# CablineDP.net
KiCad netlist of a schematic drawn in Altium Designer
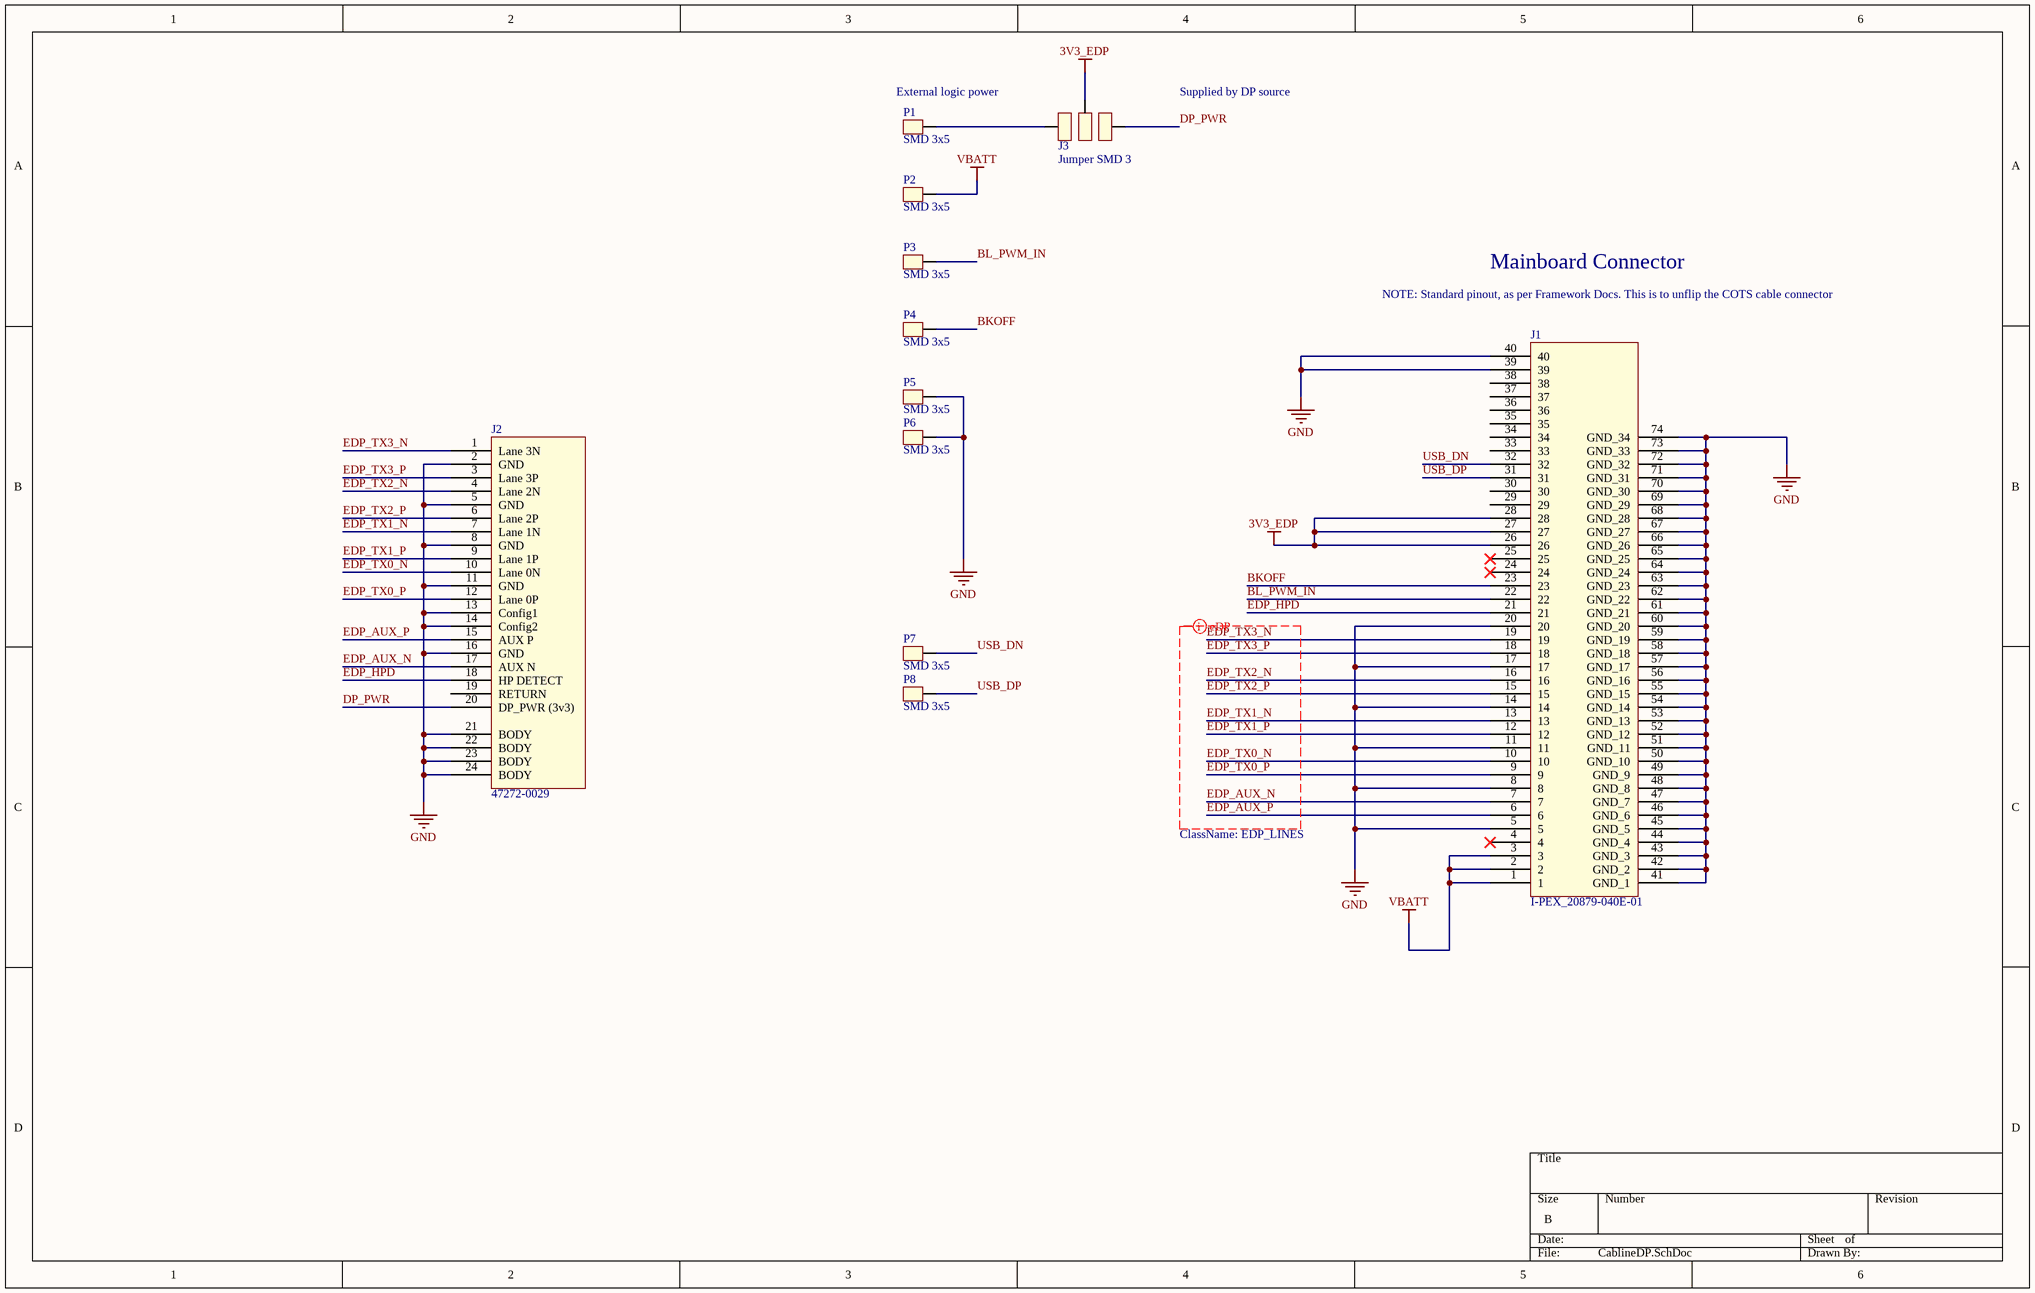
[diagram p0: CablineDP.SchDoc]

(export (version "E")
  (design (tool "Eeschema 10.0.6"))
  (components
    (comp (ref "J1")
      (value "I-PEX_20879-040E-01")
      (footprint "I-PEX_20879-040E-01")
      (libsource (lib "KBuchka-IntLib") (part "I-PEX_20879-040E-01"))
    )
    (comp (ref "J2")
      (value "47272-0029")
      (footprint "47272-0029")
      (description "Molex displayport connector")
      (libsource (lib "KBuchka-IntLib") (part "47272-0029"))
    )
    (comp (ref "J3")
      (value "Jumper SMD 3")
      (footprint "Jumper SMD 3")
      (libsource (lib "KBuchka-IntLib") (part "Jumper SMD 3"))
    )
    (comp (ref "P1")
      (value "SMD 3x5")
      (footprint "SMD 3x5")
      (libsource (lib "KBuchka-IntLib") (part "SMD 3x5"))
    )
    (comp (ref "P2")
      (value "SMD 3x5")
      (footprint "SMD 3x5")
      (libsource (lib "KBuchka-IntLib") (part "SMD 3x5"))
    )
    (comp (ref "P3")
      (value "SMD 3x5")
      (footprint "SMD 3x5")
      (libsource (lib "KBuchka-IntLib") (part "SMD 3x5"))
    )
    (comp (ref "P4")
      (value "SMD 3x5")
      (footprint "SMD 3x5")
      (libsource (lib "KBuchka-IntLib") (part "SMD 3x5"))
    )
    (comp (ref "P5")
      (value "SMD 3x5")
      (footprint "SMD 3x5")
      (libsource (lib "KBuchka-IntLib") (part "SMD 3x5"))
    )
    (comp (ref "P6")
      (value "SMD 3x5")
      (footprint "SMD 3x5")
      (libsource (lib "KBuchka-IntLib") (part "SMD 3x5"))
    )
    (comp (ref "P7")
      (value "SMD 3x5")
      (footprint "SMD 3x5")
      (libsource (lib "KBuchka-IntLib") (part "SMD 3x5"))
    )
    (comp (ref "P8")
      (value "SMD 3x5")
      (footprint "SMD 3x5")
      (libsource (lib "KBuchka-IntLib") (part "SMD 3x5"))
    )
  )
  (nets
    (net (code "1") (name "/BKOFF") (class "Default")
      (node (ref "J1") (pin "23") (pinfunction "23_23") (pintype "passive"))
      (node (ref "P4") (pin "1") (pinfunction "1_1") (pintype "passive"))
    )
    (net (code "2") (name "/BL_PWM_IN") (class "Default")
      (node (ref "J1") (pin "22") (pinfunction "22_22") (pintype "passive"))
      (node (ref "P3") (pin "1") (pinfunction "1_1") (pintype "passive"))
    )
    (net (code "3") (name "/DP_PWR") (class "Default")
      (node (ref "J2") (pin "20") (pinfunction "DP_PWR_(3v3)_20") (pintype "passive"))
      (node (ref "J3") (pin "1") (pinfunction "1_1") (pintype "passive"))
    )
    (net (code "4") (name "/EDP_AUX_N") (class "Default")
      (node (ref "J1") (pin "7") (pinfunction "7_7") (pintype "passive"))
      (node (ref "J2") (pin "17") (pinfunction "AUX_N_17") (pintype "passive"))
    )
    (net (code "5") (name "/EDP_AUX_P") (class "Default")
      (node (ref "J1") (pin "6") (pinfunction "6_6") (pintype "passive"))
      (node (ref "J2") (pin "15") (pinfunction "AUX_P_15") (pintype "passive"))
    )
    (net (code "6") (name "/EDP_HPD") (class "Default")
      (node (ref "J1") (pin "21") (pinfunction "21_21") (pintype "passive"))
      (node (ref "J2") (pin "18") (pinfunction "HP_DETECT_18") (pintype "passive"))
    )
    (net (code "7") (name "/EDP_TX0_N") (class "Default")
      (node (ref "J1") (pin "10") (pinfunction "10_10") (pintype "passive"))
      (node (ref "J2") (pin "10") (pinfunction "Lane_0N_10") (pintype "passive"))
    )
    (net (code "8") (name "/EDP_TX0_P") (class "Default")
      (node (ref "J1") (pin "9") (pinfunction "9_9") (pintype "passive"))
      (node (ref "J2") (pin "12") (pinfunction "Lane_0P_12") (pintype "passive"))
    )
    (net (code "9") (name "/EDP_TX1_N") (class "Default")
      (node (ref "J1") (pin "13") (pinfunction "13_13") (pintype "passive"))
      (node (ref "J2") (pin "7") (pinfunction "Lane_1N_7") (pintype "passive"))
    )
    (net (code "10") (name "/EDP_TX1_P") (class "Default")
      (node (ref "J1") (pin "12") (pinfunction "12_12") (pintype "passive"))
      (node (ref "J2") (pin "9") (pinfunction "Lane_1P_9") (pintype "passive"))
    )
    (net (code "11") (name "/EDP_TX2_N") (class "Default")
      (node (ref "J1") (pin "16") (pinfunction "16_16") (pintype "passive"))
      (node (ref "J2") (pin "4") (pinfunction "Lane_2N_4") (pintype "passive"))
    )
    (net (code "12") (name "/EDP_TX2_P") (class "Default")
      (node (ref "J1") (pin "15") (pinfunction "15_15") (pintype "passive"))
      (node (ref "J2") (pin "6") (pinfunction "Lane_2P_6") (pintype "passive"))
    )
    (net (code "13") (name "/EDP_TX3_N") (class "Default")
      (node (ref "J1") (pin "19") (pinfunction "19_19") (pintype "passive"))
      (node (ref "J2") (pin "1") (pinfunction "Lane_3N_1") (pintype "passive"))
    )
    (net (code "14") (name "/EDP_TX3_P") (class "Default")
      (node (ref "J1") (pin "18") (pinfunction "18_18") (pintype "passive"))
      (node (ref "J2") (pin "3") (pinfunction "Lane_3P_3") (pintype "passive"))
    )
    (net (code "15") (name "/USB_DN") (class "Default")
      (node (ref "J1") (pin "32") (pinfunction "32_32") (pintype "passive"))
      (node (ref "P7") (pin "1") (pinfunction "1_1") (pintype "passive"))
    )
    (net (code "16") (name "/USB_DP") (class "Default")
      (node (ref "J1") (pin "31") (pinfunction "31_31") (pintype "passive"))
      (node (ref "P8") (pin "1") (pinfunction "1_1") (pintype "passive"))
    )
    (net (code "17") (name "3V3_EDP") (class "Default")
      (node (ref "J1") (pin "26") (pinfunction "26_26") (pintype "passive"))
      (node (ref "J1") (pin "27") (pinfunction "27_27") (pintype "passive"))
      (node (ref "J1") (pin "28") (pinfunction "28_28") (pintype "passive"))
      (node (ref "J3") (pin "2") (pinfunction "2_2") (pintype "passive"))
    )
    (net (code "18") (name "GND") (class "Default")
      (node (ref "J1") (pin "11") (pinfunction "11_11") (pintype "passive"))
      (node (ref "J1") (pin "14") (pinfunction "14_14") (pintype "passive"))
      (node (ref "J1") (pin "17") (pinfunction "17_17") (pintype "passive"))
      (node (ref "J1") (pin "20") (pinfunction "20_20") (pintype "passive"))
      (node (ref "J1") (pin "39") (pinfunction "39_39") (pintype "passive"))
      (node (ref "J1") (pin "40") (pinfunction "40_40") (pintype "passive"))
      (node (ref "J1") (pin "41") (pinfunction "GND_1_41") (pintype "passive"))
      (node (ref "J1") (pin "42") (pinfunction "GND_2_42") (pintype "passive"))
      (node (ref "J1") (pin "43") (pinfunction "GND_3_43") (pintype "passive"))
      (node (ref "J1") (pin "44") (pinfunction "GND_4_44") (pintype "passive"))
      (node (ref "J1") (pin "45") (pinfunction "GND_5_45") (pintype "passive"))
      (node (ref "J1") (pin "46") (pinfunction "GND_6_46") (pintype "passive"))
      (node (ref "J1") (pin "47") (pinfunction "GND_7_47") (pintype "passive"))
      (node (ref "J1") (pin "48") (pinfunction "GND_8_48") (pintype "passive"))
      (node (ref "J1") (pin "49") (pinfunction "GND_9_49") (pintype "passive"))
      (node (ref "J1") (pin "5") (pinfunction "5_5") (pintype "passive"))
      (node (ref "J1") (pin "50") (pinfunction "GND_10_50") (pintype "passive"))
      (node (ref "J1") (pin "51") (pinfunction "GND_11_51") (pintype "passive"))
      (node (ref "J1") (pin "52") (pinfunction "GND_12_52") (pintype "passive"))
      (node (ref "J1") (pin "53") (pinfunction "GND_13_53") (pintype "passive"))
      (node (ref "J1") (pin "54") (pinfunction "GND_14_54") (pintype "passive"))
      (node (ref "J1") (pin "55") (pinfunction "GND_15_55") (pintype "passive"))
      (node (ref "J1") (pin "56") (pinfunction "GND_16_56") (pintype "passive"))
      (node (ref "J1") (pin "57") (pinfunction "GND_17_57") (pintype "passive"))
      (node (ref "J1") (pin "58") (pinfunction "GND_18_58") (pintype "passive"))
      (node (ref "J1") (pin "59") (pinfunction "GND_19_59") (pintype "passive"))
      (node (ref "J1") (pin "60") (pinfunction "GND_20_60") (pintype "passive"))
      (node (ref "J1") (pin "61") (pinfunction "GND_21_61") (pintype "passive"))
      (node (ref "J1") (pin "62") (pinfunction "GND_22_62") (pintype "passive"))
      (node (ref "J1") (pin "63") (pinfunction "GND_23_63") (pintype "passive"))
      (node (ref "J1") (pin "64") (pinfunction "GND_24_64") (pintype "passive"))
      (node (ref "J1") (pin "65") (pinfunction "GND_25_65") (pintype "passive"))
      (node (ref "J1") (pin "66") (pinfunction "GND_26_66") (pintype "passive"))
      (node (ref "J1") (pin "67") (pinfunction "GND_27_67") (pintype "passive"))
      (node (ref "J1") (pin "68") (pinfunction "GND_28_68") (pintype "passive"))
      (node (ref "J1") (pin "69") (pinfunction "GND_29_69") (pintype "passive"))
      (node (ref "J1") (pin "70") (pinfunction "GND_30_70") (pintype "passive"))
      (node (ref "J1") (pin "71") (pinfunction "GND_31_71") (pintype "passive"))
      (node (ref "J1") (pin "72") (pinfunction "GND_32_72") (pintype "passive"))
      (node (ref "J1") (pin "73") (pinfunction "GND_33_73") (pintype "passive"))
      (node (ref "J1") (pin "74") (pinfunction "GND_34_74") (pintype "passive"))
      (node (ref "J1") (pin "8") (pinfunction "8_8") (pintype "passive"))
      (node (ref "J2") (pin "11") (pinfunction "GND_11") (pintype "passive"))
      (node (ref "J2") (pin "13") (pinfunction "Config1_13") (pintype "passive"))
      (node (ref "J2") (pin "14") (pinfunction "Config2_14") (pintype "passive"))
      (node (ref "J2") (pin "16") (pinfunction "GND_16") (pintype "passive"))
      (node (ref "J2") (pin "2") (pinfunction "GND_2") (pintype "passive"))
      (node (ref "J2") (pin "21") (pinfunction "BODY_21") (pintype "passive"))
      (node (ref "J2") (pin "22") (pinfunction "BODY_22") (pintype "passive"))
      (node (ref "J2") (pin "23") (pinfunction "BODY_23") (pintype "passive"))
      (node (ref "J2") (pin "24") (pinfunction "BODY_24") (pintype "passive"))
      (node (ref "J2") (pin "5") (pinfunction "GND_5") (pintype "passive"))
      (node (ref "J2") (pin "8") (pinfunction "GND_8") (pintype "passive"))
      (node (ref "P5") (pin "1") (pinfunction "1_1") (pintype "passive"))
      (node (ref "P6") (pin "1") (pinfunction "1_1") (pintype "passive"))
    )
    (net (code "19") (name "Net-(J3-Pad3)") (class "Default")
      (node (ref "J3") (pin "3") (pinfunction "3_3") (pintype "passive"))
      (node (ref "P1") (pin "1") (pinfunction "1_1") (pintype "passive"))
    )
    (net (code "20") (name "VBATT") (class "Default")
      (node (ref "J1") (pin "1") (pinfunction "1_1") (pintype "passive"))
      (node (ref "J1") (pin "2") (pinfunction "2_2") (pintype "passive"))
      (node (ref "J1") (pin "3") (pinfunction "3_3") (pintype "passive"))
      (node (ref "P2") (pin "1") (pinfunction "1_1") (pintype "passive"))
    )
    (net (code "21") (name "unconnected-(J1-Pad4)") (class "Default")
      (node (ref "J1") (pin "4") (pinfunction "4_4") (pintype "passive+no_connect"))
    )
    (net (code "22") (name "unconnected-(J1-Pad24)") (class "Default")
      (node (ref "J1") (pin "24") (pinfunction "24_24") (pintype "passive+no_connect"))
    )
    (net (code "23") (name "unconnected-(J1-Pad25)") (class "Default")
      (node (ref "J1") (pin "25") (pinfunction "25_25") (pintype "passive+no_connect"))
    )
    (net (code "24") (name "unconnected-(J1-Pad29)") (class "Default")
      (node (ref "J1") (pin "29") (pinfunction "29_29") (pintype "passive"))
    )
    (net (code "25") (name "unconnected-(J1-Pad30)") (class "Default")
      (node (ref "J1") (pin "30") (pinfunction "30_30") (pintype "passive"))
    )
    (net (code "26") (name "unconnected-(J1-Pad33)") (class "Default")
      (node (ref "J1") (pin "33") (pinfunction "33_33") (pintype "passive"))
    )
    (net (code "27") (name "unconnected-(J1-Pad34)") (class "Default")
      (node (ref "J1") (pin "34") (pinfunction "34_34") (pintype "passive"))
    )
    (net (code "28") (name "unconnected-(J1-Pad35)") (class "Default")
      (node (ref "J1") (pin "35") (pinfunction "35_35") (pintype "passive"))
    )
    (net (code "29") (name "unconnected-(J1-Pad36)") (class "Default")
      (node (ref "J1") (pin "36") (pinfunction "36_36") (pintype "passive"))
    )
    (net (code "30") (name "unconnected-(J1-Pad37)") (class "Default")
      (node (ref "J1") (pin "37") (pinfunction "37_37") (pintype "passive"))
    )
    (net (code "31") (name "unconnected-(J1-Pad38)") (class "Default")
      (node (ref "J1") (pin "38") (pinfunction "38_38") (pintype "passive"))
    )
    (net (code "32") (name "unconnected-(J2-RETURN-Pad19)") (class "Default")
      (node (ref "J2") (pin "19") (pinfunction "RETURN_19") (pintype "passive"))
    )
  )
)
